# MCB1313epf.net
KiCad netlist of a schematic drawn in Altium Designer
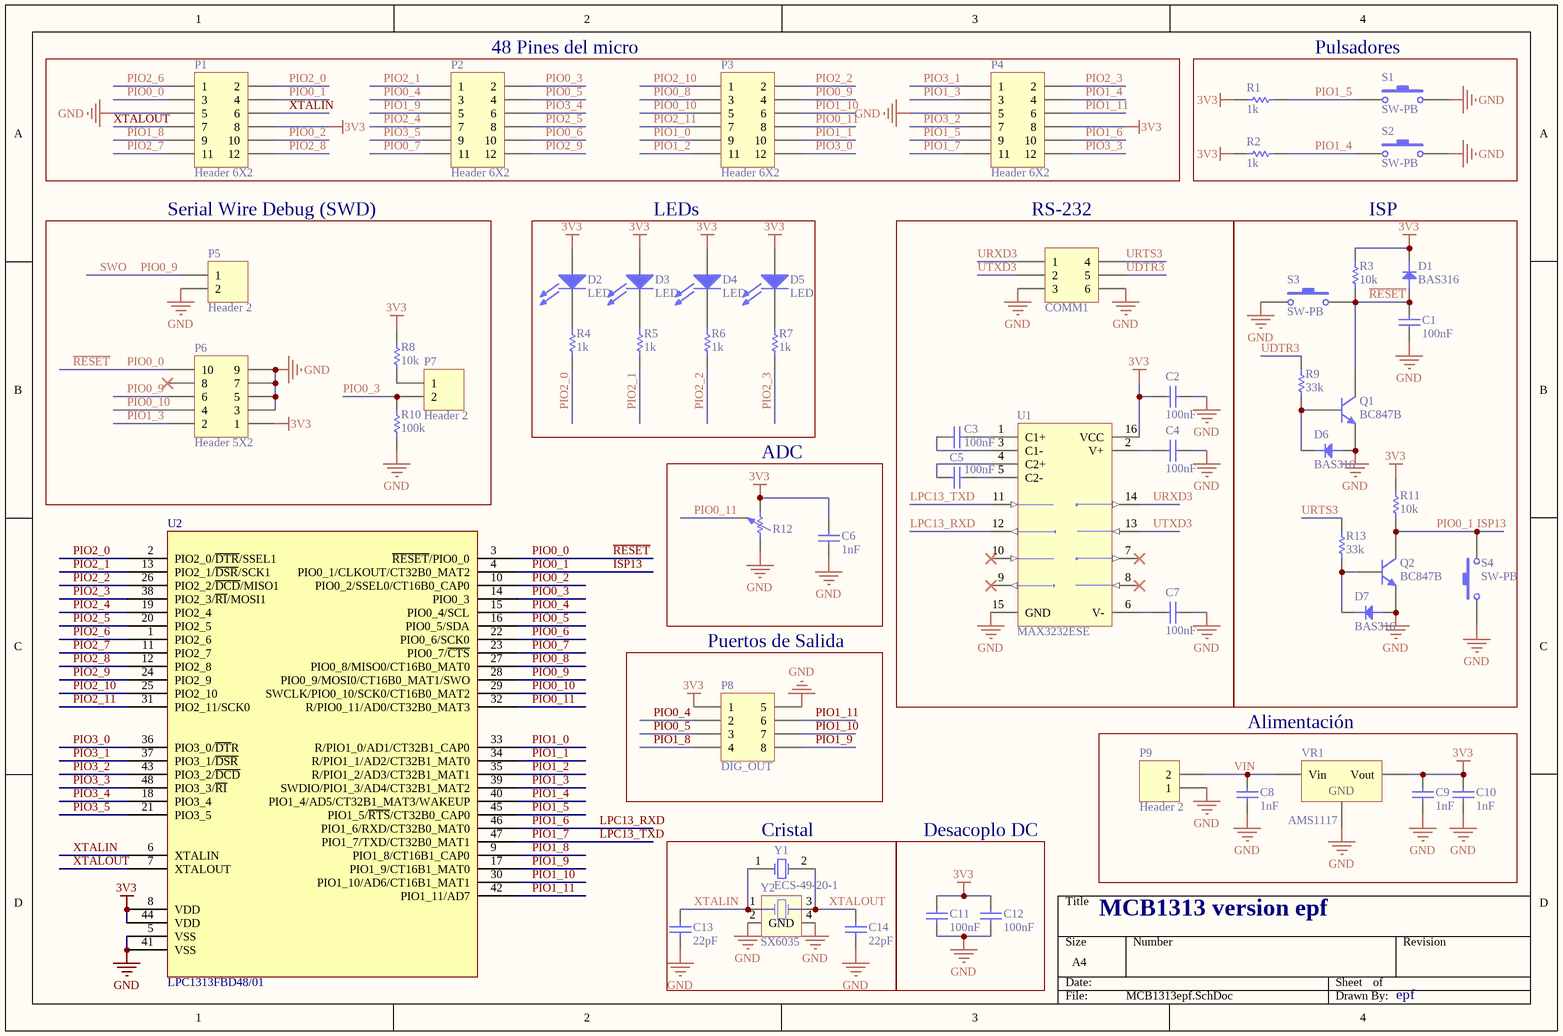
[diagram p0: MCB1313epf.SchDoc]

(export (version "E")
  (design (tool "Eeschema 10.0.6"))
  (components
    (comp (ref "C1")
      (value "100nF")
      (footprint "0805_CAP")
      (fields (field (name "Comment") "Capacitor"))
      (libsource (lib "epf") (part "Cap"))
    )
    (comp (ref "C2")
      (value "100nF")
      (footprint "0805_CAP")
      (fields (field (name "Comment") "Capacitor"))
      (libsource (lib "epf") (part "Cap"))
    )
    (comp (ref "C3")
      (value "100nF")
      (footprint "0805_CAP")
      (fields (field (name "Comment") "Capacitor"))
      (libsource (lib "epf") (part "Cap"))
    )
    (comp (ref "C4")
      (value "100nF")
      (footprint "0805_CAP")
      (fields (field (name "Comment") "Capacitor"))
      (libsource (lib "epf") (part "Cap"))
    )
    (comp (ref "C5")
      (value "100nF")
      (footprint "0805_CAP")
      (fields (field (name "Comment") "Capacitor"))
      (libsource (lib "epf") (part "Cap"))
    )
    (comp (ref "C6")
      (value "1nF")
      (footprint "0805_CAP")
      (fields (field (name "Comment") "Capacitor"))
      (libsource (lib "epf") (part "Cap"))
    )
    (comp (ref "C7")
      (value "100nF")
      (footprint "0805_CAP")
      (fields (field (name "Comment") "Capacitor"))
      (libsource (lib "epf") (part "Cap"))
    )
    (comp (ref "C8")
      (value "1nF")
      (footprint "0805_CAP")
      (fields (field (name "Comment") "Capacitor"))
      (libsource (lib "epf") (part "Cap"))
    )
    (comp (ref "C9")
      (value "1nF")
      (footprint "0805_CAP")
      (fields (field (name "Comment") "Capacitor"))
      (libsource (lib "epf") (part "Cap"))
    )
    (comp (ref "C10")
      (value "1nF")
      (footprint "0805_CAP")
      (fields (field (name "Comment") "Capacitor"))
      (libsource (lib "epf") (part "Cap"))
    )
    (comp (ref "C11")
      (value "100nF")
      (footprint "0805_CAP")
      (fields (field (name "Comment") "Capacitor"))
      (libsource (lib "epf") (part "Cap"))
    )
    (comp (ref "C12")
      (value "100nF")
      (footprint "0805_CAP")
      (fields (field (name "Comment") "Capacitor"))
      (libsource (lib "epf") (part "Cap"))
    )
    (comp (ref "C13")
      (value "22pF")
      (footprint "0805_CAP")
      (fields (field (name "Comment") "Capacitor"))
      (libsource (lib "epf") (part "Cap"))
    )
    (comp (ref "C14")
      (value "22pF")
      (footprint "0805_CAP")
      (fields (field (name "Comment") "Capacitor"))
      (libsource (lib "epf") (part "Cap"))
    )
    (comp (ref "COMM1")
      (value "AP_COMM")
      (footprint "HDR2X3_CEN")
      (description "Header, 3-Pin, Dual row")
      (fields (field (name "PUBLISHER") "Altium Limited"))
      (libsource (lib "epf") (part "AP_COMM"))
    )
    (comp (ref "D1") (value "BAS316") (footprint "SOD-323") (libsource (lib "epf") (part "BAS316")))
    (comp (ref "D2") (value "LED") (footprint "LED0603") (libsource (lib "epf") (part "LED1")))
    (comp (ref "D3") (value "LED") (footprint "LED0603") (libsource (lib "epf") (part "LED1")))
    (comp (ref "D4") (value "LED") (footprint "LED0603") (libsource (lib "epf") (part "LED1")))
    (comp (ref "D5") (value "LED") (footprint "LED0603") (libsource (lib "epf") (part "LED1")))
    (comp (ref "D6") (value "BAS316") (footprint "SOD-323") (libsource (lib "epf") (part "BAS316")))
    (comp (ref "D7") (value "BAS316") (footprint "SOD-323") (libsource (lib "epf") (part "BAS316")))
    (comp (ref "P1")
      (value "Header 6X2")
      (footprint "HDR2X6")
      (description "Header, 6-Pin, Dual row")
      (fields (field (name "PUBLISHER") "Altium Limited"))
      (libsource (lib "Miscellaneous Connectors") (part "Header 6X2"))
    )
    (comp (ref "P2")
      (value "Header 6X2")
      (footprint "HDR2X6")
      (description "Header, 6-Pin, Dual row")
      (fields (field (name "PUBLISHER") "Altium Limited"))
      (libsource (lib "Miscellaneous Connectors") (part "Header 6X2"))
    )
    (comp (ref "P3")
      (value "Header 6X2")
      (footprint "HDR2X6")
      (description "Header, 6-Pin, Dual row")
      (fields (field (name "PUBLISHER") "Altium Limited"))
      (libsource (lib "Miscellaneous Connectors") (part "Header 6X2"))
    )
    (comp (ref "P4")
      (value "Header 6X2")
      (footprint "HDR2X6")
      (description "Header, 6-Pin, Dual row")
      (fields (field (name "PUBLISHER") "Altium Limited"))
      (libsource (lib "Miscellaneous Connectors") (part "Header 6X2"))
    )
    (comp (ref "P5")
      (value "Header 2")
      (footprint "HDR1X2")
      (description "Header, 2-Pin")
      (fields (field (name "PUBLISHER") "Altium Limited"))
      (libsource (lib "Miscellaneous Connectors") (part "Header 2"))
    )
    (comp (ref "P6")
      (value "Header 5X2")
      (footprint "HDR2X5")
      (description "Header, 5-Pin, Dual row")
      (fields (field (name "PUBLISHER") "Altium Limited"))
      (libsource (lib "epf") (part "Header 5X2"))
    )
    (comp (ref "P7")
      (value "Header 2")
      (footprint "HDR1X2")
      (description "Header, 2-Pin")
      (fields (field (name "PUBLISHER") "Altium Limited"))
      (libsource (lib "Miscellaneous Connectors") (part "Header 2"))
    )
    (comp (ref "P8")
      (value "DIG_OUT")
      (footprint "HDR2X4_CEN")
      (description "Header, 4-Pin, Dual row")
      (fields (field (name "PUBLISHER") "Altium Limited"))
      (libsource (lib "epf") (part "AP_SALIDA_DIGITAL"))
    )
    (comp (ref "P9")
      (value "Header 2")
      (footprint "HDR1X2")
      (description "Header, 2-Pin")
      (fields (field (name "PUBLISHER") "Altium Limited"))
      (libsource (lib "") (part "Header 2_1"))
    )
    (comp (ref "Q1")
      (value "BC847B")
      (footprint "SOT23")
      (description "NPN 100MHz")
      (libsource (lib "epf") (part "BC847B"))
    )
    (comp (ref "Q2")
      (value "BC847B")
      (footprint "SOT23")
      (description "NPN 100MHz")
      (libsource (lib "epf") (part "BC847B"))
    )
    (comp (ref "R1")
      (value "1k")
      (footprint "0805_RES")
      (fields (field (name "Comment") "Resistor"))
      (libsource (lib "epf") (part "Res"))
    )
    (comp (ref "R2")
      (value "1k")
      (footprint "0805_RES")
      (fields (field (name "Comment") "Resistor"))
      (libsource (lib "epf") (part "Res"))
    )
    (comp (ref "R3")
      (value "10k")
      (footprint "0805_RES")
      (fields (field (name "Comment") "Resistor"))
      (libsource (lib "epf") (part "Res"))
    )
    (comp (ref "R4")
      (value "1k")
      (footprint "0805_RES")
      (fields (field (name "Comment") "Resistor"))
      (libsource (lib "epf") (part "Res"))
    )
    (comp (ref "R5")
      (value "1k")
      (footprint "0805_RES")
      (fields (field (name "Comment") "Resistor"))
      (libsource (lib "epf") (part "Res"))
    )
    (comp (ref "R6")
      (value "1k")
      (footprint "0805_RES")
      (fields (field (name "Comment") "Resistor"))
      (libsource (lib "epf") (part "Res"))
    )
    (comp (ref "R7")
      (value "1k")
      (footprint "0805_RES")
      (fields (field (name "Comment") "Resistor"))
      (libsource (lib "epf") (part "Res"))
    )
    (comp (ref "R8")
      (value "10k")
      (footprint "0805_RES")
      (fields (field (name "Comment") "Resistor"))
      (libsource (lib "epf") (part "Res"))
    )
    (comp (ref "R9")
      (value "33k")
      (footprint "0805_RES")
      (fields (field (name "Comment") "Resistor"))
      (libsource (lib "epf") (part "Res"))
    )
    (comp (ref "R10")
      (value "100k")
      (footprint "0805_RES")
      (fields (field (name "Comment") "Resistor"))
      (libsource (lib "epf") (part "Res"))
    )
    (comp (ref "R11")
      (value "10k")
      (footprint "0805_RES")
      (fields (field (name "Comment") "Resistor"))
      (libsource (lib "epf") (part "Res"))
    )
    (comp (ref "R12") (value "Pot") (footprint "POT_SMD") (libsource (lib "epf") (part "Pot")))
    (comp (ref "R13")
      (value "33k")
      (footprint "0805_RES")
      (fields (field (name "Comment") "Resistor"))
      (libsource (lib "epf") (part "Res"))
    )
    (comp (ref "S1")
      (value "SW-PB")
      (footprint "SW-PB6mm - 2")
      (description "Switch")
      (fields (field (name "PUBLISHER") "Altium Limited"))
      (libsource (lib "epf") (part "SW-PB"))
    )
    (comp (ref "S2")
      (value "SW-PB")
      (footprint "SW-PB6mm - 2")
      (description "Switch")
      (fields (field (name "PUBLISHER") "Altium Limited"))
      (libsource (lib "epf") (part "SW-PB"))
    )
    (comp (ref "S3")
      (value "SW-PB")
      (footprint "SW-PB6mm - 2")
      (description "Switch")
      (fields (field (name "PUBLISHER") "Altium Limited"))
      (libsource (lib "epf") (part "SW-PB"))
    )
    (comp (ref "S4")
      (value "SW-PB")
      (footprint "SW-PB6mm - 2")
      (description "Switch")
      (fields (field (name "PUBLISHER") "Altium Limited"))
      (libsource (lib "epf") (part "SW-PB"))
    )
    (comp (ref "U1")
      (value "MAX3232ESE")
      (footprint "SOIC127P602-16BN")
      (libsource (lib "epf") (part "MAX3232ESE+"))
    )
    (comp (ref "U2")
      (value "LPC1313FBD48/01")
      (footprint "TQFP48_LPC1343")
      (description "ARM CortexM3 32K Flash, 8k RAM")
      (libsource (lib "epf") (part "LPC1313FBD48/01"))
    )
    (comp (ref "VR1")
      (value "AMS1117")
      (footprint "SOT-223 - M3")
      (description "Voltage Regulator")
      (fields (field (name "PUBLISHER") "Altium Limited"))
      (libsource (lib "epf") (part "AMS1117"))
    )
    (comp (ref "Y1")
      (value "ECS-49-20-1")
      (footprint "HC-49U")
      (description "Crystal Oscillator")
      (fields (field (name "PUBLISHER") "Altium Limited"))
      (libsource (lib "ECS Crystal Oscillator") (part "ECS-49-20-1"))
    )
    (comp (ref "Y2") (value "SX6035") (footprint "SX6035") (libsource (lib "epf") (part "XTAL_SX6035")))
  )
  (nets
    (net (code "1") (name "/ISP13") (class "Default")
      (node (ref "P1") (pin "4") (pinfunction "4_4") (pintype "passive"))
      (node (ref "Q2") (pin "3") (pinfunction "C_3") (pintype "passive"))
      (node (ref "R11") (pin "1") (pinfunction "1_1") (pintype "passive"))
      (node (ref "S4") (pin "2") (pinfunction "2_2") (pintype "passive"))
      (node (ref "U2") (pin "4") (pinfunction "PIO0_1/CLKOUT/CT32B0_MAT2_4") (pintype "passive"))
    )
    (net (code "2") (name "/LPC13_RXD") (class "Default")
      (node (ref "P4") (pin "10") (pinfunction "10_10") (pintype "passive"))
      (node (ref "U1") (pin "12") (pinfunction "R1OUT_12") (pintype "output"))
      (node (ref "U2") (pin "46") (pinfunction "PIO1_6/RXD/CT32B0_MAT0_46") (pintype "passive"))
    )
    (net (code "3") (name "/LPC13_TXD") (class "Default")
      (node (ref "P4") (pin "11") (pinfunction "11_11") (pintype "passive"))
      (node (ref "U1") (pin "11") (pinfunction "T1IN_11") (pintype "input"))
      (node (ref "U2") (pin "47") (pinfunction "PIO1_7/TXD/CT32B0_MAT1_47") (pintype "passive"))
    )
    (net (code "4") (name "/PIO0_0") (class "Default")
      (node (ref "C1") (pin "1") (pinfunction "1_1") (pintype "passive"))
      (node (ref "D1") (pin "2") (pinfunction "A_2") (pintype "passive"))
      (node (ref "P1") (pin "3") (pinfunction "3_3") (pintype "passive"))
      (node (ref "P6") (pin "10") (pinfunction "10_10") (pintype "passive"))
      (node (ref "Q1") (pin "3") (pinfunction "C_3") (pintype "passive"))
      (node (ref "R3") (pin "1") (pinfunction "1_1") (pintype "passive"))
      (node (ref "S3") (pin "2") (pinfunction "2_2") (pintype "passive"))
      (node (ref "U2") (pin "3") (pinfunction "~{RESET}/PIO0_0_3") (pintype "passive"))
    )
    (net (code "5") (name "/PIO0_2") (class "Default")
      (node (ref "P1") (pin "10") (pinfunction "10_10") (pintype "passive"))
      (node (ref "U2") (pin "10") (pinfunction "PIO0_2/SSEL0/CT16B0_CAP0_10") (pintype "passive"))
    )
    (net (code "6") (name "/PIO0_3") (class "Default")
      (node (ref "P2") (pin "2") (pinfunction "2_2") (pintype "passive"))
      (node (ref "P7") (pin "2") (pinfunction "2_2") (pintype "passive"))
      (node (ref "R10") (pin "1") (pinfunction "1_1") (pintype "passive"))
      (node (ref "U2") (pin "14") (pinfunction "PIO0_3_14") (pintype "passive"))
    )
    (net (code "7") (name "/PIO0_4") (class "Default")
      (node (ref "P2") (pin "3") (pinfunction "3_3") (pintype "passive"))
      (node (ref "P8") (pin "2") (pinfunction "2_2") (pintype "passive"))
      (node (ref "U2") (pin "15") (pinfunction "PIO0_4/SCL_15") (pintype "passive"))
    )
    (net (code "8") (name "/PIO0_5") (class "Default")
      (node (ref "P2") (pin "4") (pinfunction "4_4") (pintype "passive"))
      (node (ref "P8") (pin "3") (pinfunction "3_3") (pintype "passive"))
      (node (ref "U2") (pin "16") (pinfunction "PIO0_5/SDA_16") (pintype "passive"))
    )
    (net (code "9") (name "/PIO0_6") (class "Default")
      (node (ref "P2") (pin "10") (pinfunction "10_10") (pintype "passive"))
      (node (ref "U2") (pin "22") (pinfunction "PIO0_6/SCK0_22") (pintype "passive"))
    )
    (net (code "10") (name "/PIO0_7") (class "Default")
      (node (ref "P2") (pin "11") (pinfunction "11_11") (pintype "passive"))
      (node (ref "U2") (pin "23") (pinfunction "PIO0_7/~{CTS}_23") (pintype "passive"))
    )
    (net (code "11") (name "/PIO0_8") (class "Default")
      (node (ref "P3") (pin "3") (pinfunction "3_3") (pintype "passive"))
      (node (ref "U2") (pin "27") (pinfunction "PIO0_8/MISO0/CT16B0_MAT0_27") (pintype "passive"))
    )
    (net (code "12") (name "/PIO0_9") (class "Default")
      (node (ref "P3") (pin "4") (pinfunction "4_4") (pintype "passive"))
      (node (ref "P5") (pin "1") (pinfunction "1_1") (pintype "passive"))
      (node (ref "P6") (pin "6") (pinfunction "6_6") (pintype "passive"))
      (node (ref "U2") (pin "28") (pinfunction "PIO0_9/MOSI0/CT16B0_MAT1/SWO_28") (pintype "passive"))
    )
    (net (code "13") (name "/PIO0_10") (class "Default")
      (node (ref "P3") (pin "5") (pinfunction "5_5") (pintype "passive"))
      (node (ref "P6") (pin "4") (pinfunction "4_4") (pintype "passive"))
      (node (ref "U2") (pin "29") (pinfunction "SWCLK/PIO0_10/SCK0/CT16B0_MAT2_29") (pintype "passive"))
    )
    (net (code "14") (name "/PIO0_11") (class "Default")
      (node (ref "P3") (pin "8") (pinfunction "8_8") (pintype "passive"))
      (node (ref "R12") (pin "3") (pinfunction "3_3") (pintype "passive"))
      (node (ref "U2") (pin "32") (pinfunction "R/PIO0_11/AD0/CT32B0_MAT3_32") (pintype "passive"))
    )
    (net (code "15") (name "/PIO1_0") (class "Default")
      (node (ref "P3") (pin "9") (pinfunction "9_9") (pintype "passive"))
      (node (ref "U2") (pin "33") (pinfunction "R/PIO1_0/AD1/CT32B1_CAP0_33") (pintype "passive"))
    )
    (net (code "16") (name "/PIO1_1") (class "Default")
      (node (ref "P3") (pin "10") (pinfunction "10_10") (pintype "passive"))
      (node (ref "U2") (pin "34") (pinfunction "R/PIO1_1/AD2/CT32B1_MAT0_34") (pintype "passive"))
    )
    (net (code "17") (name "/PIO1_2") (class "Default")
      (node (ref "P3") (pin "11") (pinfunction "11_11") (pintype "passive"))
      (node (ref "U2") (pin "35") (pinfunction "R/PIO1_2/AD3/CT32B1_MAT1_35") (pintype "passive"))
    )
    (net (code "18") (name "/PIO1_3") (class "Default")
      (node (ref "P4") (pin "3") (pinfunction "3_3") (pintype "passive"))
      (node (ref "P6") (pin "2") (pinfunction "2_2") (pintype "passive"))
      (node (ref "U2") (pin "39") (pinfunction "SWDIO/PIO1_3/AD4/CT32B1_MAT2_39") (pintype "passive"))
    )
    (net (code "19") (name "/PIO1_4") (class "Default")
      (node (ref "P4") (pin "4") (pinfunction "4_4") (pintype "passive"))
      (node (ref "R2") (pin "2") (pinfunction "2_2") (pintype "passive"))
      (node (ref "S2") (pin "1") (pinfunction "1_1") (pintype "passive"))
      (node (ref "U2") (pin "40") (pinfunction "PIO1_4/AD5/CT32B1_MAT3/WAKEUP_40") (pintype "passive"))
    )
    (net (code "20") (name "/PIO1_5") (class "Default")
      (node (ref "P4") (pin "9") (pinfunction "9_9") (pintype "passive"))
      (node (ref "R1") (pin "2") (pinfunction "2_2") (pintype "passive"))
      (node (ref "S1") (pin "1") (pinfunction "1_1") (pintype "passive"))
      (node (ref "U2") (pin "45") (pinfunction "PIO1_5/~{RTS}/CT32B0_CAP0_45") (pintype "passive"))
    )
    (net (code "21") (name "/PIO1_8") (class "Default")
      (node (ref "P1") (pin "9") (pinfunction "9_9") (pintype "passive"))
      (node (ref "P8") (pin "4") (pinfunction "4_4") (pintype "passive"))
      (node (ref "U2") (pin "9") (pinfunction "PIO1_8/CT16B1_CAP0_9") (pintype "passive"))
    )
    (net (code "22") (name "/PIO1_9") (class "Default")
      (node (ref "P2") (pin "5") (pinfunction "5_5") (pintype "passive"))
      (node (ref "P8") (pin "8") (pinfunction "8_8") (pintype "passive"))
      (node (ref "U2") (pin "17") (pinfunction "PIO1_9/CT16B1_MAT0_17") (pintype "passive"))
    )
    (net (code "23") (name "/PIO1_10") (class "Default")
      (node (ref "P3") (pin "6") (pinfunction "6_6") (pintype "passive"))
      (node (ref "P8") (pin "7") (pinfunction "7_7") (pintype "passive"))
      (node (ref "U2") (pin "30") (pinfunction "PIO1_10/AD6/CT16B1_MAT1_30") (pintype "passive"))
    )
    (net (code "24") (name "/PIO1_11") (class "Default")
      (node (ref "P4") (pin "6") (pinfunction "6_6") (pintype "passive"))
      (node (ref "P8") (pin "6") (pinfunction "6_6") (pintype "passive"))
      (node (ref "U2") (pin "42") (pinfunction "PIO1_11/AD7_42") (pintype "passive"))
    )
    (net (code "25") (name "/PIO2_0") (class "Default")
      (node (ref "P1") (pin "2") (pinfunction "2_2") (pintype "passive"))
      (node (ref "R4") (pin "2") (pinfunction "2_2") (pintype "passive"))
      (node (ref "U2") (pin "2") (pinfunction "PIO2_0/~{DTR}/SSEL1_2") (pintype "passive"))
    )
    (net (code "26") (name "/PIO2_1") (class "Default")
      (node (ref "P2") (pin "1") (pinfunction "1_1") (pintype "passive"))
      (node (ref "R5") (pin "2") (pinfunction "2_2") (pintype "passive"))
      (node (ref "U2") (pin "13") (pinfunction "PIO2_1/~{DSR}/SCK1_13") (pintype "passive"))
    )
    (net (code "27") (name "/PIO2_2") (class "Default")
      (node (ref "P3") (pin "2") (pinfunction "2_2") (pintype "passive"))
      (node (ref "R6") (pin "2") (pinfunction "2_2") (pintype "passive"))
      (node (ref "U2") (pin "26") (pinfunction "PIO2_2/~{DCD}/MISO1_26") (pintype "passive"))
    )
    (net (code "28") (name "/PIO2_3") (class "Default")
      (node (ref "P4") (pin "2") (pinfunction "2_2") (pintype "passive"))
      (node (ref "R7") (pin "2") (pinfunction "2_2") (pintype "passive"))
      (node (ref "U2") (pin "38") (pinfunction "PIO2_3/~{RI}/MOSI1_38") (pintype "passive"))
    )
    (net (code "29") (name "/PIO2_4") (class "Default")
      (node (ref "P2") (pin "7") (pinfunction "7_7") (pintype "passive"))
      (node (ref "U2") (pin "19") (pinfunction "PIO2_4_19") (pintype "passive"))
    )
    (net (code "30") (name "/PIO2_5") (class "Default")
      (node (ref "P2") (pin "8") (pinfunction "8_8") (pintype "passive"))
      (node (ref "U2") (pin "20") (pinfunction "PIO2_5_20") (pintype "passive"))
    )
    (net (code "31") (name "/PIO2_6") (class "Default")
      (node (ref "P1") (pin "1") (pinfunction "1_1") (pintype "passive"))
      (node (ref "U2") (pin "1") (pinfunction "PIO2_6_1") (pintype "passive"))
    )
    (net (code "32") (name "/PIO2_7") (class "Default")
      (node (ref "P1") (pin "11") (pinfunction "11_11") (pintype "passive"))
      (node (ref "U2") (pin "11") (pinfunction "PIO2_7_11") (pintype "passive"))
    )
    (net (code "33") (name "/PIO2_8") (class "Default")
      (node (ref "P1") (pin "12") (pinfunction "12_12") (pintype "passive"))
      (node (ref "U2") (pin "12") (pinfunction "PIO2_8_12") (pintype "passive"))
    )
    (net (code "34") (name "/PIO2_9") (class "Default")
      (node (ref "P2") (pin "12") (pinfunction "12_12") (pintype "passive"))
      (node (ref "U2") (pin "24") (pinfunction "PIO2_9_24") (pintype "passive"))
    )
    (net (code "35") (name "/PIO2_10") (class "Default")
      (node (ref "P3") (pin "1") (pinfunction "1_1") (pintype "passive"))
      (node (ref "U2") (pin "25") (pinfunction "PIO2_10_25") (pintype "passive"))
    )
    (net (code "36") (name "/PIO2_11") (class "Default")
      (node (ref "P3") (pin "7") (pinfunction "7_7") (pintype "passive"))
      (node (ref "U2") (pin "31") (pinfunction "PIO2_11/SCK0_31") (pintype "passive"))
    )
    (net (code "37") (name "/PIO3_0") (class "Default")
      (node (ref "P3") (pin "12") (pinfunction "12_12") (pintype "passive"))
      (node (ref "U2") (pin "36") (pinfunction "PIO3_0/~{DT}R_36") (pintype "passive"))
    )
    (net (code "38") (name "/PIO3_1") (class "Default")
      (node (ref "P4") (pin "1") (pinfunction "1_1") (pintype "passive"))
      (node (ref "U2") (pin "37") (pinfunction "PIO3_1/~{DSR}_37") (pintype "passive"))
    )
    (net (code "39") (name "/PIO3_2") (class "Default")
      (node (ref "P4") (pin "7") (pinfunction "7_7") (pintype "passive"))
      (node (ref "U2") (pin "43") (pinfunction "PIO3_2/~{DCD}_43") (pintype "passive"))
    )
    (net (code "40") (name "/PIO3_3") (class "Default")
      (node (ref "P4") (pin "12") (pinfunction "12_12") (pintype "passive"))
      (node (ref "U2") (pin "48") (pinfunction "PIO3_3/~{RI}_48") (pintype "passive"))
    )
    (net (code "41") (name "/PIO3_4") (class "Default")
      (node (ref "P2") (pin "6") (pinfunction "6_6") (pintype "passive"))
      (node (ref "U2") (pin "18") (pinfunction "PIO3_4_18") (pintype "passive"))
    )
    (net (code "42") (name "/PIO3_5") (class "Default")
      (node (ref "P2") (pin "9") (pinfunction "9_9") (pintype "passive"))
      (node (ref "U2") (pin "21") (pinfunction "PIO3_5_21") (pintype "passive"))
    )
    (net (code "43") (name "/UDTR3") (class "Default")
      (node (ref "COMM1") (pin "5") (pinfunction "5_5") (pintype "passive"))
      (node (ref "R9") (pin "2") (pinfunction "2_2") (pintype "passive"))
    )
    (net (code "44") (name "/URTS3") (class "Default")
      (node (ref "COMM1") (pin "4") (pinfunction "4_4") (pintype "passive"))
      (node (ref "R13") (pin "2") (pinfunction "2_2") (pintype "passive"))
    )
    (net (code "45") (name "/URXD3") (class "Default")
      (node (ref "COMM1") (pin "1") (pinfunction "1_1") (pintype "passive"))
      (node (ref "U1") (pin "14") (pinfunction "T1OUT_14") (pintype "output"))
    )
    (net (code "46") (name "/UTXD3") (class "Default")
      (node (ref "COMM1") (pin "2") (pinfunction "2_2") (pintype "passive"))
      (node (ref "U1") (pin "13") (pinfunction "R1IN_13") (pintype "input"))
    )
    (net (code "47") (name "/VIN") (class "Default")
      (node (ref "C8") (pin "2") (pinfunction "2_2") (pintype "passive"))
      (node (ref "P9") (pin "2") (pinfunction "2_2") (pintype "passive"))
      (node (ref "VR1") (pin "3") (pinfunction "Vin_3") (pintype "passive"))
    )
    (net (code "48") (name "/XTALIN") (class "Default")
      (node (ref "C13") (pin "2") (pinfunction "2_2") (pintype "passive"))
      (node (ref "P1") (pin "6") (pinfunction "6_6") (pintype "passive"))
      (node (ref "U2") (pin "6") (pinfunction "XTALIN_6") (pintype "passive"))
      (node (ref "Y1") (pin "1") (pinfunction "OSC1_1") (pintype "passive"))
      (node (ref "Y2") (pin "1") (pinfunction "XTAL_1") (pintype "passive"))
    )
    (net (code "49") (name "/XTALOUT") (class "Default")
      (node (ref "C14") (pin "1") (pinfunction "1_1") (pintype "passive"))
      (node (ref "P1") (pin "7") (pinfunction "7_7") (pintype "passive"))
      (node (ref "U2") (pin "7") (pinfunction "XTALOUT_7") (pintype "passive"))
      (node (ref "Y1") (pin "2") (pinfunction "OSC2_2") (pintype "passive"))
      (node (ref "Y2") (pin "3") (pinfunction "XTAL_3") (pintype "passive"))
    )
    (net (code "50") (name "3V3") (class "Default")
      (node (ref "C10") (pin "2") (pinfunction "2_2") (pintype "passive"))
      (node (ref "C11") (pin "2") (pinfunction "2_2") (pintype "passive"))
      (node (ref "C12") (pin "2") (pinfunction "2_2") (pintype "passive"))
      (node (ref "C2") (pin "2") (pinfunction "2_2") (pintype "passive"))
      (node (ref "C6") (pin "2") (pinfunction "2_2") (pintype "passive"))
      (node (ref "C9") (pin "2") (pinfunction "2_2") (pintype "passive"))
      (node (ref "D1") (pin "1") (pinfunction "K_1") (pintype "passive"))
      (node (ref "D2") (pin "1") (pinfunction "A_1") (pintype "passive"))
      (node (ref "D3") (pin "1") (pinfunction "A_1") (pintype "passive"))
      (node (ref "D4") (pin "1") (pinfunction "A_1") (pintype "passive"))
      (node (ref "D5") (pin "1") (pinfunction "A_1") (pintype "passive"))
      (node (ref "P1") (pin "8") (pinfunction "8_8") (pintype "passive"))
      (node (ref "P4") (pin "8") (pinfunction "8_8") (pintype "passive"))
      (node (ref "P6") (pin "1") (pinfunction "1_1") (pintype "passive"))
      (node (ref "P8") (pin "1") (pinfunction "1_1") (pintype "passive"))
      (node (ref "R1") (pin "1") (pinfunction "1_1") (pintype "passive"))
      (node (ref "R11") (pin "2") (pinfunction "2_2") (pintype "passive"))
      (node (ref "R12") (pin "2") (pinfunction "2_2") (pintype "passive"))
      (node (ref "R2") (pin "1") (pinfunction "1_1") (pintype "passive"))
      (node (ref "R3") (pin "2") (pinfunction "2_2") (pintype "passive"))
      (node (ref "R8") (pin "1") (pinfunction "1_1") (pintype "passive"))
      (node (ref "U1") (pin "16") (pinfunction "VCC_16") (pintype "power_in"))
      (node (ref "U2") (pin "44") (pinfunction "VDD_44") (pintype "passive"))
      (node (ref "U2") (pin "8") (pinfunction "VDD_8") (pintype "passive"))
      (node (ref "VR1") (pin "2") (pinfunction "Vout_2") (pintype "passive"))
    )
    (net (code "51") (name "GND") (class "Default")
      (node (ref "C1") (pin "2") (pinfunction "2_2") (pintype "passive"))
      (node (ref "C10") (pin "1") (pinfunction "1_1") (pintype "passive"))
      (node (ref "C11") (pin "1") (pinfunction "1_1") (pintype "passive"))
      (node (ref "C12") (pin "1") (pinfunction "1_1") (pintype "passive"))
      (node (ref "C13") (pin "1") (pinfunction "1_1") (pintype "passive"))
      (node (ref "C14") (pin "2") (pinfunction "2_2") (pintype "passive"))
      (node (ref "C2") (pin "1") (pinfunction "1_1") (pintype "passive"))
      (node (ref "C4") (pin "1") (pinfunction "1_1") (pintype "passive"))
      (node (ref "C6") (pin "1") (pinfunction "1_1") (pintype "passive"))
      (node (ref "C7") (pin "1") (pinfunction "1_1") (pintype "passive"))
      (node (ref "C8") (pin "1") (pinfunction "1_1") (pintype "passive"))
      (node (ref "C9") (pin "1") (pinfunction "1_1") (pintype "passive"))
      (node (ref "COMM1") (pin "3") (pinfunction "3_3") (pintype "passive"))
      (node (ref "COMM1") (pin "6") (pinfunction "6_6") (pintype "passive"))
      (node (ref "D6") (pin "2") (pinfunction "A_2") (pintype "passive"))
      (node (ref "D7") (pin "2") (pinfunction "A_2") (pintype "passive"))
      (node (ref "P1") (pin "5") (pinfunction "5_5") (pintype "passive"))
      (node (ref "P4") (pin "5") (pinfunction "5_5") (pintype "passive"))
      (node (ref "P5") (pin "2") (pinfunction "2_2") (pintype "passive"))
      (node (ref "P6") (pin "3") (pinfunction "3_3") (pintype "passive"))
      (node (ref "P6") (pin "5") (pinfunction "5_5") (pintype "passive"))
      (node (ref "P6") (pin "7") (pinfunction "7_7") (pintype "passive"))
      (node (ref "P6") (pin "9") (pinfunction "9_9") (pintype "passive"))
      (node (ref "P8") (pin "5") (pinfunction "5_5") (pintype "passive"))
      (node (ref "P9") (pin "1") (pinfunction "1_1") (pintype "passive"))
      (node (ref "Q1") (pin "2") (pinfunction "E_2") (pintype "passive"))
      (node (ref "Q2") (pin "2") (pinfunction "E_2") (pintype "passive"))
      (node (ref "R10") (pin "2") (pinfunction "2_2") (pintype "passive"))
      (node (ref "R12") (pin "1") (pinfunction "1_1") (pintype "passive"))
      (node (ref "S1") (pin "2") (pinfunction "2_2") (pintype "passive"))
      (node (ref "S2") (pin "2") (pinfunction "2_2") (pintype "passive"))
      (node (ref "S3") (pin "1") (pinfunction "1_1") (pintype "passive"))
      (node (ref "S4") (pin "1") (pinfunction "1_1") (pintype "passive"))
      (node (ref "U1") (pin "15") (pinfunction "GND_15") (pintype "power_in"))
      (node (ref "U2") (pin "41") (pinfunction "VSS_41") (pintype "passive"))
      (node (ref "U2") (pin "5") (pinfunction "VSS_5") (pintype "passive"))
      (node (ref "VR1") (pin "1") (pinfunction "GND_1") (pintype "passive"))
      (node (ref "Y2") (pin "2") (pinfunction "GND_2") (pintype "passive"))
      (node (ref "Y2") (pin "4") (pinfunction "GND_4") (pintype "passive"))
    )
    (net (code "52") (name "Net-(D2-K)") (class "Default")
      (node (ref "D2") (pin "2") (pinfunction "K_2") (pintype "passive"))
      (node (ref "R4") (pin "1") (pinfunction "1_1") (pintype "passive"))
    )
    (net (code "53") (name "Net-(D3-K)") (class "Default")
      (node (ref "D3") (pin "2") (pinfunction "K_2") (pintype "passive"))
      (node (ref "R5") (pin "1") (pinfunction "1_1") (pintype "passive"))
    )
    (net (code "54") (name "Net-(D4-K)") (class "Default")
      (node (ref "D4") (pin "2") (pinfunction "K_2") (pintype "passive"))
      (node (ref "R6") (pin "1") (pinfunction "1_1") (pintype "passive"))
    )
    (net (code "55") (name "Net-(D5-K)") (class "Default")
      (node (ref "D5") (pin "2") (pinfunction "K_2") (pintype "passive"))
      (node (ref "R7") (pin "1") (pinfunction "1_1") (pintype "passive"))
    )
    (net (code "56") (name "Net-(D6-K)") (class "Default")
      (node (ref "D6") (pin "1") (pinfunction "K_1") (pintype "passive"))
      (node (ref "Q1") (pin "1") (pinfunction "B_1") (pintype "passive"))
      (node (ref "R9") (pin "1") (pinfunction "1_1") (pintype "passive"))
    )
    (net (code "57") (name "Net-(D7-K)") (class "Default")
      (node (ref "D7") (pin "1") (pinfunction "K_1") (pintype "passive"))
      (node (ref "Q2") (pin "1") (pinfunction "B_1") (pintype "passive"))
      (node (ref "R13") (pin "1") (pinfunction "1_1") (pintype "passive"))
    )
    (net (code "58") (name "Net-(P7-Pad1)") (class "Default")
      (node (ref "P7") (pin "1") (pinfunction "1_1") (pintype "passive"))
      (node (ref "R8") (pin "2") (pinfunction "2_2") (pintype "passive"))
    )
    (net (code "59") (name "Net-(U1-C1+)") (class "Default")
      (node (ref "C3") (pin "1") (pinfunction "1_1") (pintype "passive"))
      (node (ref "U1") (pin "1") (pinfunction "C1+_1") (pintype "passive"))
    )
    (net (code "60") (name "Net-(U1-C1-)") (class "Default")
      (node (ref "C3") (pin "2") (pinfunction "2_2") (pintype "passive"))
      (node (ref "U1") (pin "3") (pinfunction "C1-_3") (pintype "passive"))
    )
    (net (code "61") (name "Net-(U1-C2+)") (class "Default")
      (node (ref "C5") (pin "2") (pinfunction "2_2") (pintype "passive"))
      (node (ref "U1") (pin "4") (pinfunction "C2+_4") (pintype "passive"))
    )
    (net (code "62") (name "Net-(U1-C2-)") (class "Default")
      (node (ref "C5") (pin "1") (pinfunction "1_1") (pintype "passive"))
      (node (ref "U1") (pin "5") (pinfunction "C2-_5") (pintype "passive"))
    )
    (net (code "63") (name "Net-(U1-V+)") (class "Default")
      (node (ref "C4") (pin "2") (pinfunction "2_2") (pintype "passive"))
      (node (ref "U1") (pin "2") (pinfunction "V+_2") (pintype "power_in"))
    )
    (net (code "64") (name "Net-(U1-V-)") (class "Default")
      (node (ref "C7") (pin "2") (pinfunction "2_2") (pintype "passive"))
      (node (ref "U1") (pin "6") (pinfunction "V-_6") (pintype "power_in"))
    )
    (net (code "65") (name "unconnected-(P6-Pad8)") (class "Default")
      (node (ref "P6") (pin "8") (pinfunction "8_8") (pintype "passive+no_connect"))
    )
    (net (code "66") (name "unconnected-(U1-R2IN-Pad8)") (class "Default")
      (node (ref "U1") (pin "8") (pinfunction "R2IN_8") (pintype "input+no_connect"))
    )
    (net (code "67") (name "unconnected-(U1-R2OUT-Pad9)") (class "Default")
      (node (ref "U1") (pin "9") (pinfunction "R2OUT_9") (pintype "output+no_connect"))
    )
    (net (code "68") (name "unconnected-(U1-T2IN-Pad10)") (class "Default")
      (node (ref "U1") (pin "10") (pinfunction "T2IN_10") (pintype "input+no_connect"))
    )
    (net (code "69") (name "unconnected-(U1-T2OUT-Pad7)") (class "Default")
      (node (ref "U1") (pin "7") (pinfunction "T2OUT_7") (pintype "output+no_connect"))
    )
  )
)
